# HID2AMI_Deluxe_Rev1_1_0_redist.net
KiCad netlist of a schematic drawn in EAGLE
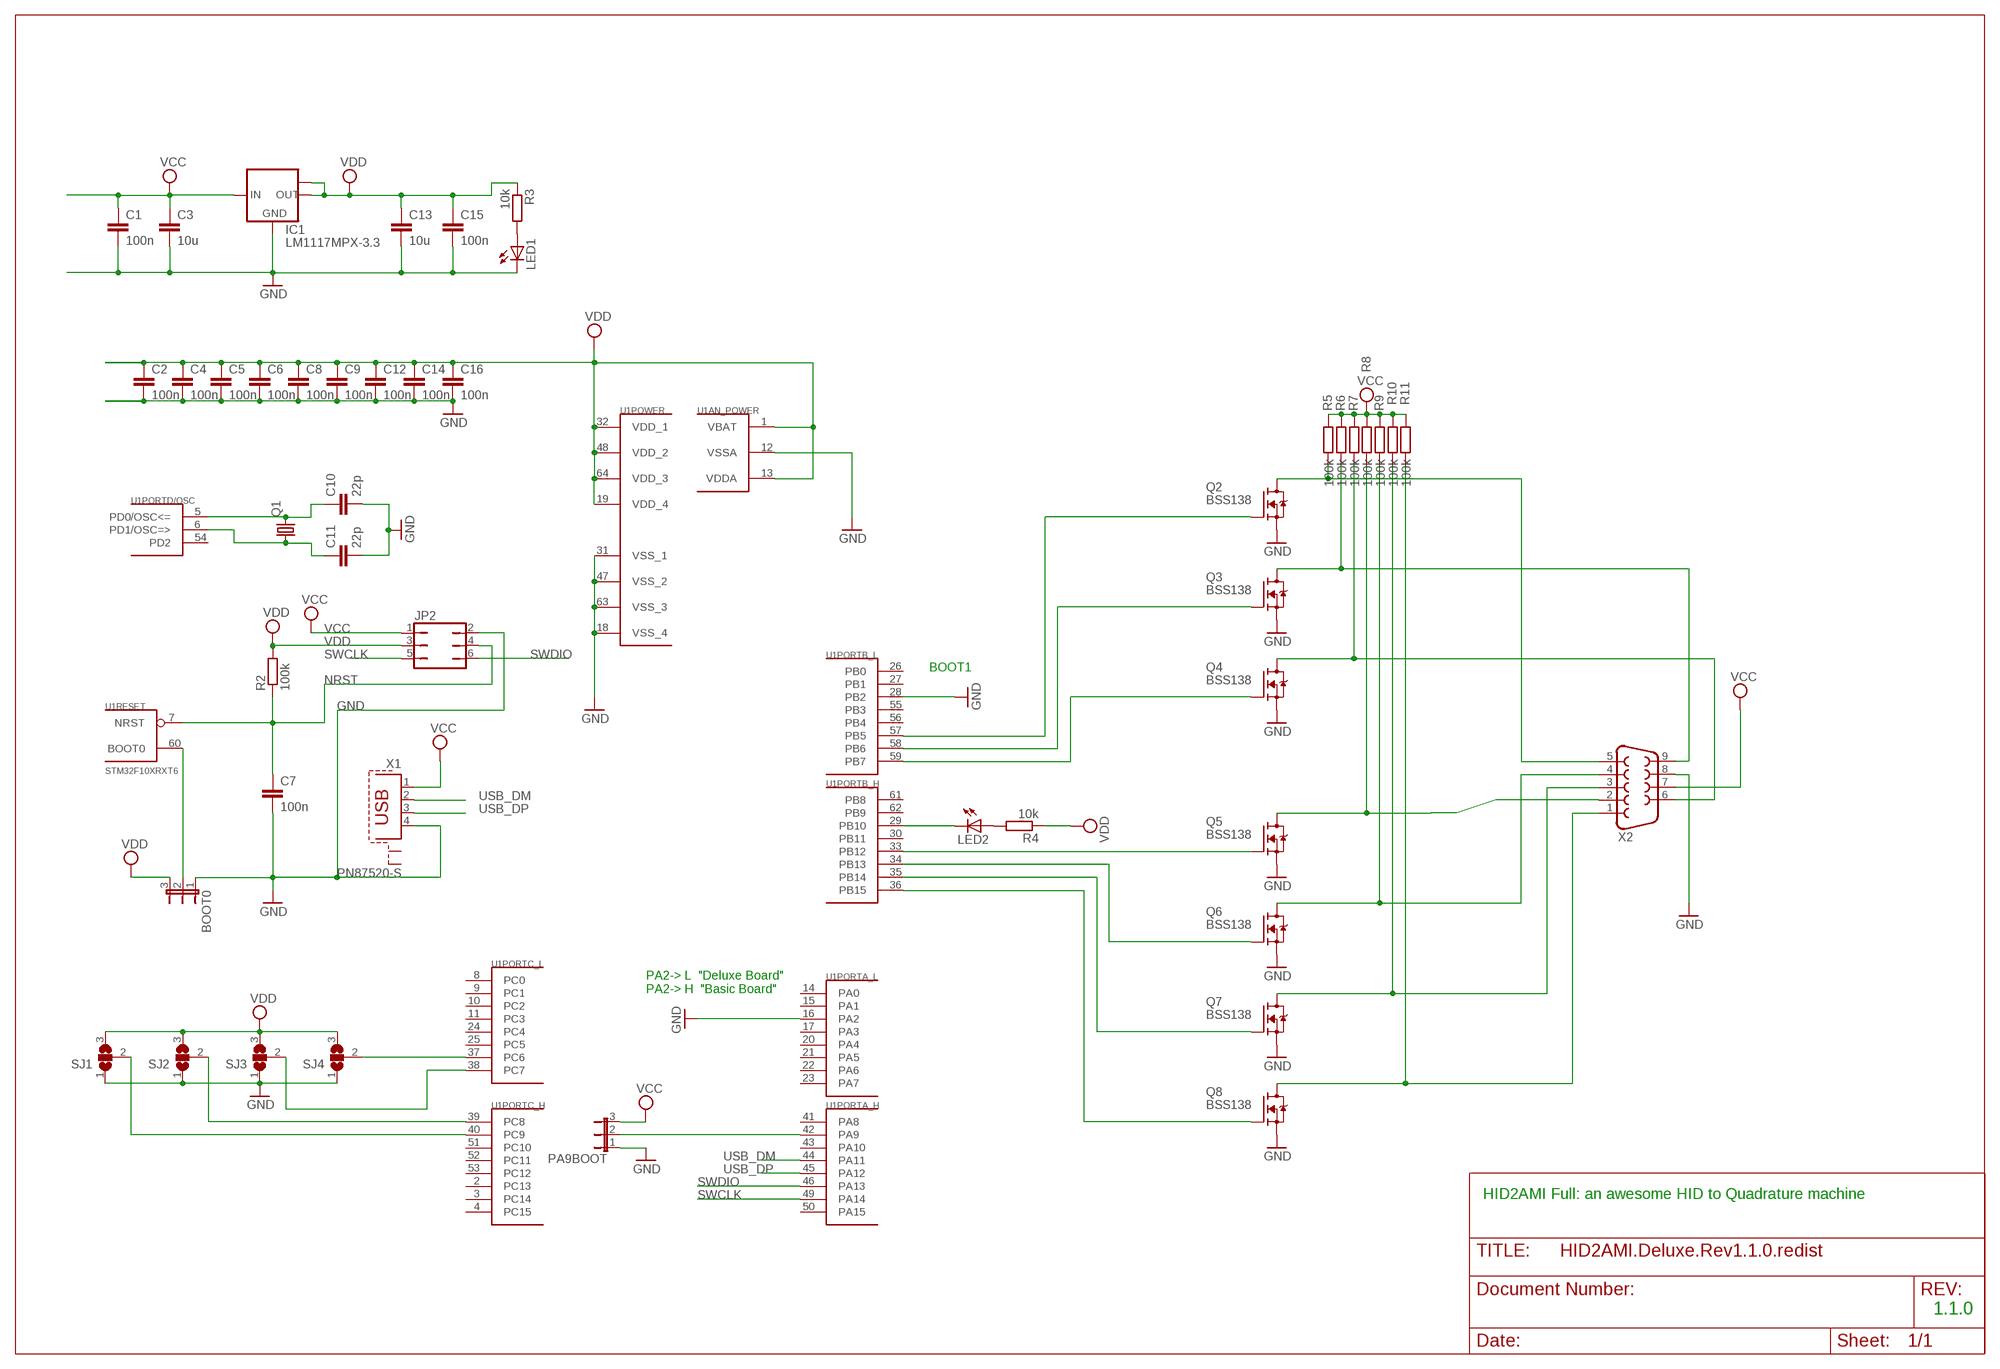
[diagram p0: schematic, sheet 1]

(export (version "E")
  (design (tool "Eeschema 10.0.6"))
  (components
    (comp (ref "BOOT0")
      (value "JP2E")
      (footprint "eagle-import:JP2")
      (libsource (lib "eagle-import") (part "JP2E"))
    )
    (comp (ref "C1")
      (value "100n")
      (footprint "eagle-import:C0805")
      (libsource (lib "eagle-import") (part "C-EUC0805"))
    )
    (comp (ref "C2")
      (value "100n")
      (footprint "eagle-import:C0805")
      (libsource (lib "eagle-import") (part "C-EUC0805"))
    )
    (comp (ref "C3")
      (value "10u")
      (footprint "eagle-import:C1206")
      (libsource (lib "eagle-import") (part "C-EUC1206"))
    )
    (comp (ref "C4")
      (value "100n")
      (footprint "eagle-import:C0805")
      (libsource (lib "eagle-import") (part "C-EUC0805"))
    )
    (comp (ref "C5")
      (value "100n")
      (footprint "eagle-import:C0805")
      (libsource (lib "eagle-import") (part "C-EUC0805"))
    )
    (comp (ref "C6")
      (value "100n")
      (footprint "eagle-import:C0805")
      (libsource (lib "eagle-import") (part "C-EUC0805"))
    )
    (comp (ref "C7")
      (value "100n")
      (footprint "eagle-import:C0805")
      (libsource (lib "eagle-import") (part "C-EUC0805"))
    )
    (comp (ref "C8")
      (value "100n")
      (footprint "eagle-import:C0805")
      (libsource (lib "eagle-import") (part "C-EUC0805"))
    )
    (comp (ref "C9")
      (value "100n")
      (footprint "eagle-import:C0805")
      (libsource (lib "eagle-import") (part "C-EUC0805"))
    )
    (comp (ref "C10")
      (value "22p")
      (footprint "eagle-import:C0805")
      (libsource (lib "eagle-import") (part "C-EUC0805"))
    )
    (comp (ref "C11")
      (value "22p")
      (footprint "eagle-import:C0805")
      (libsource (lib "eagle-import") (part "C-EUC0805"))
    )
    (comp (ref "C12")
      (value "100n")
      (footprint "eagle-import:C0805")
      (libsource (lib "eagle-import") (part "C-EUC0805"))
    )
    (comp (ref "C13")
      (value "10u")
      (footprint "eagle-import:C0805")
      (libsource (lib "eagle-import") (part "C-EUC0805"))
    )
    (comp (ref "C14")
      (value "100n")
      (footprint "eagle-import:C0805")
      (libsource (lib "eagle-import") (part "C-EUC0805"))
    )
    (comp (ref "C15")
      (value "100n")
      (footprint "eagle-import:C0805")
      (libsource (lib "eagle-import") (part "C-EUC0805"))
    )
    (comp (ref "C16")
      (value "100n")
      (footprint "eagle-import:C0805")
      (libsource (lib "eagle-import") (part "C-EUC0805"))
    )
    (comp (ref "IC1")
      (value "LM1117MPX-3.3")
      (footprint "eagle-import:SOT223")
      (libsource (lib "eagle-import") (part "LM1117MPX-3.3"))
    )
    (comp (ref "JP2")
      (value "JP3Q")
      (footprint "eagle-import:JP3Q")
      (libsource (lib "eagle-import") (part "JP3Q"))
    )
    (comp (ref "LED1")
      (value "LEDSML0805")
      (footprint "eagle-import:SML0805")
      (libsource (lib "eagle-import") (part "LEDSML0805"))
    )
    (comp (ref "LED2")
      (value "LEDSML0805")
      (footprint "eagle-import:SML0805")
      (libsource (lib "eagle-import") (part "LEDSML0805"))
    )
    (comp (ref "PA9BOOT")
      (value "JP2E")
      (footprint "eagle-import:JP2")
      (libsource (lib "eagle-import") (part "JP2E"))
    )
    (comp (ref "Q1")
      (value "CRYSTALHC49S")
      (footprint "eagle-import:HC49_S")
      (libsource (lib "eagle-import") (part "CRYSTALHC49S"))
    )
    (comp (ref "Q2")
      (value "BSS138")
      (footprint "eagle-import:SOT23")
      (fields (field (name "MF") "Fairchild"))
      (libsource (lib "eagle-import") (part "BSS138"))
    )
    (comp (ref "Q3")
      (value "BSS138")
      (footprint "eagle-import:SOT23")
      (fields (field (name "MF") "Fairchild"))
      (libsource (lib "eagle-import") (part "BSS138"))
    )
    (comp (ref "Q4")
      (value "BSS138")
      (footprint "eagle-import:SOT23")
      (fields (field (name "MF") "Fairchild"))
      (libsource (lib "eagle-import") (part "BSS138"))
    )
    (comp (ref "Q5")
      (value "BSS138")
      (footprint "eagle-import:SOT23")
      (fields (field (name "MF") "Fairchild"))
      (libsource (lib "eagle-import") (part "BSS138"))
    )
    (comp (ref "Q6")
      (value "BSS138")
      (footprint "eagle-import:SOT23")
      (fields (field (name "MF") "Fairchild"))
      (libsource (lib "eagle-import") (part "BSS138"))
    )
    (comp (ref "Q7")
      (value "BSS138")
      (footprint "eagle-import:SOT23")
      (fields (field (name "MF") "Fairchild"))
      (libsource (lib "eagle-import") (part "BSS138"))
    )
    (comp (ref "Q8")
      (value "BSS138")
      (footprint "eagle-import:SOT23")
      (fields (field (name "MF") "Fairchild"))
      (libsource (lib "eagle-import") (part "BSS138"))
    )
    (comp (ref "R2")
      (value "100k")
      (footprint "eagle-import:M0805")
      (libsource (lib "eagle-import") (part "R-EU_M0805"))
    )
    (comp (ref "R3")
      (value "10k")
      (footprint "eagle-import:M0805")
      (libsource (lib "eagle-import") (part "R-EU_M0805"))
    )
    (comp (ref "R4")
      (value "10k")
      (footprint "eagle-import:M0805")
      (libsource (lib "eagle-import") (part "R-EU_M0805"))
    )
    (comp (ref "R5")
      (value "100k")
      (footprint "eagle-import:M0805")
      (libsource (lib "eagle-import") (part "R-EU_M0805"))
    )
    (comp (ref "R6")
      (value "100k")
      (footprint "eagle-import:M0805")
      (libsource (lib "eagle-import") (part "R-EU_M0805"))
    )
    (comp (ref "R7")
      (value "100k")
      (footprint "eagle-import:M0805")
      (libsource (lib "eagle-import") (part "R-EU_M0805"))
    )
    (comp (ref "R8")
      (value "100k")
      (footprint "eagle-import:M0805")
      (libsource (lib "eagle-import") (part "R-EU_M0805"))
    )
    (comp (ref "R9")
      (value "100k")
      (footprint "eagle-import:M0805")
      (libsource (lib "eagle-import") (part "R-EU_M0805"))
    )
    (comp (ref "R10")
      (value "100k")
      (footprint "eagle-import:M0805")
      (libsource (lib "eagle-import") (part "R-EU_M0805"))
    )
    (comp (ref "R11")
      (value "100k")
      (footprint "eagle-import:M0805")
      (libsource (lib "eagle-import") (part "R-EU_M0805"))
    )
    (comp (ref "SJ1")
      (value "SJ2W")
      (footprint "eagle-import:SJ_2")
      (libsource (lib "eagle-import") (part "SJ2W"))
    )
    (comp (ref "SJ2")
      (value "SJ2W")
      (footprint "eagle-import:SJ_2")
      (libsource (lib "eagle-import") (part "SJ2W"))
    )
    (comp (ref "SJ3")
      (value "SJ2W")
      (footprint "eagle-import:SJ_2")
      (libsource (lib "eagle-import") (part "SJ2W"))
    )
    (comp (ref "SJ4")
      (value "SJ2W")
      (footprint "eagle-import:SJ_2")
      (libsource (lib "eagle-import") (part "SJ2W"))
    )
    (comp (ref "U1")
      (value "STM32F10XRXT6")
      (footprint "eagle-import:TQFP64")
      (libsource (lib "eagle-import") (part "STM32F10XRXT6"))
    )
    (comp (ref "X1")
      (value "PN87520-S")
      (footprint "eagle-import:PN87520-S")
      (libsource (lib "eagle-import") (part "PN87520-S"))
    )
    (comp (ref "X2")
      (value "F09HP")
      (footprint "eagle-import:F09HP")
      (libsource (lib "eagle-import") (part "F09HP"))
    )
  )
  (nets
    (net (code "1") (name "/NRST") (class "Default")
      (node (ref "C7") (pin "1") (pinfunction "1_1") (pintype "passive"))
      (node (ref "JP2") (pin "4") (pinfunction "4_4") (pintype "passive"))
      (node (ref "R2") (pin "1") (pinfunction "1_1") (pintype "passive"))
      (node (ref "U1") (pin "7") (pinfunction "NRST_7") (pintype "input"))
    )
    (net (code "2") (name "/SWCLK") (class "Default")
      (node (ref "JP2") (pin "5") (pinfunction "5_5") (pintype "passive"))
      (node (ref "U1") (pin "49") (pinfunction "PA14_49") (pintype "bidirectional"))
    )
    (net (code "3") (name "/SWDIO") (class "Default")
      (node (ref "JP2") (pin "6") (pinfunction "6_6") (pintype "passive"))
      (node (ref "U1") (pin "46") (pinfunction "PA13_46") (pintype "bidirectional"))
    )
    (net (code "4") (name "/USB_DM") (class "Default")
      (node (ref "U1") (pin "44") (pinfunction "PA11_44") (pintype "bidirectional"))
      (node (ref "X1") (pin "2") (pinfunction "2_2") (pintype "passive"))
    )
    (net (code "5") (name "/USB_DP") (class "Default")
      (node (ref "U1") (pin "45") (pinfunction "PA12_45") (pintype "bidirectional"))
      (node (ref "X1") (pin "3") (pinfunction "3_3") (pintype "passive"))
    )
    (net (code "6") (name "GND") (class "Default")
      (node (ref "BOOT0") (pin "1") (pinfunction "1_1") (pintype "passive"))
      (node (ref "C1") (pin "2") (pinfunction "2_2") (pintype "passive"))
      (node (ref "C10") (pin "2") (pinfunction "2_2") (pintype "passive"))
      (node (ref "C11") (pin "2") (pinfunction "2_2") (pintype "passive"))
      (node (ref "C12") (pin "2") (pinfunction "2_2") (pintype "passive"))
      (node (ref "C13") (pin "2") (pinfunction "2_2") (pintype "passive"))
      (node (ref "C14") (pin "2") (pinfunction "2_2") (pintype "passive"))
      (node (ref "C15") (pin "2") (pinfunction "2_2") (pintype "passive"))
      (node (ref "C16") (pin "2") (pinfunction "2_2") (pintype "passive"))
      (node (ref "C2") (pin "2") (pinfunction "2_2") (pintype "passive"))
      (node (ref "C3") (pin "2") (pinfunction "2_2") (pintype "passive"))
      (node (ref "C4") (pin "2") (pinfunction "2_2") (pintype "passive"))
      (node (ref "C5") (pin "2") (pinfunction "2_2") (pintype "passive"))
      (node (ref "C6") (pin "2") (pinfunction "2_2") (pintype "passive"))
      (node (ref "C7") (pin "2") (pinfunction "2_2") (pintype "passive"))
      (node (ref "C8") (pin "2") (pinfunction "2_2") (pintype "passive"))
      (node (ref "C9") (pin "2") (pinfunction "2_2") (pintype "passive"))
      (node (ref "IC1") (pin "1") (pinfunction "GND_1") (pintype "input"))
      (node (ref "JP2") (pin "2") (pinfunction "2_2") (pintype "passive"))
      (node (ref "LED1") (pin "C") (pinfunction "C_C") (pintype "passive"))
      (node (ref "PA9BOOT") (pin "1") (pinfunction "1_1") (pintype "passive"))
      (node (ref "Q2") (pin "2") (pinfunction "S_2") (pintype "passive"))
      (node (ref "Q3") (pin "2") (pinfunction "S_2") (pintype "passive"))
      (node (ref "Q4") (pin "2") (pinfunction "S_2") (pintype "passive"))
      (node (ref "Q5") (pin "2") (pinfunction "S_2") (pintype "passive"))
      (node (ref "Q6") (pin "2") (pinfunction "S_2") (pintype "passive"))
      (node (ref "Q7") (pin "2") (pinfunction "S_2") (pintype "passive"))
      (node (ref "Q8") (pin "2") (pinfunction "S_2") (pintype "passive"))
      (node (ref "SJ1") (pin "1") (pinfunction "1_1") (pintype "passive"))
      (node (ref "SJ2") (pin "1") (pinfunction "1_1") (pintype "passive"))
      (node (ref "SJ3") (pin "1") (pinfunction "1_1") (pintype "passive"))
      (node (ref "SJ4") (pin "1") (pinfunction "1_1") (pintype "passive"))
      (node (ref "U1") (pin "12") (pinfunction "VSSA_12") (pintype "power_in"))
      (node (ref "U1") (pin "16") (pinfunction "PA2_16") (pintype "bidirectional"))
      (node (ref "U1") (pin "18") (pinfunction "VSS_4_18") (pintype "power_in"))
      (node (ref "U1") (pin "28") (pinfunction "PB2_28") (pintype "bidirectional"))
      (node (ref "U1") (pin "31") (pinfunction "VSS_1_31") (pintype "power_in"))
      (node (ref "U1") (pin "47") (pinfunction "VSS_2_47") (pintype "power_in"))
      (node (ref "U1") (pin "63") (pinfunction "VSS_3_63") (pintype "power_in"))
      (node (ref "X1") (pin "4") (pinfunction "4_4") (pintype "passive"))
      (node (ref "X2") (pin "8") (pinfunction "8_8") (pintype "passive"))
    )
    (net (code "7") (name "Net-(LED1-PadA)") (class "Default")
      (node (ref "LED1") (pin "A") (pinfunction "A_A") (pintype "passive"))
      (node (ref "R3") (pin "2") (pinfunction "2_2") (pintype "passive"))
    )
    (net (code "8") (name "Net-(LED2-PadA)") (class "Default")
      (node (ref "LED2") (pin "A") (pinfunction "A_A") (pintype "passive"))
      (node (ref "R4") (pin "2") (pinfunction "2_2") (pintype "passive"))
    )
    (net (code "9") (name "Net-(Q2-D)") (class "Default")
      (node (ref "Q2") (pin "3") (pinfunction "D_3") (pintype "passive"))
      (node (ref "R5") (pin "2") (pinfunction "2_2") (pintype "passive"))
      (node (ref "X2") (pin "5") (pinfunction "5_5") (pintype "passive"))
    )
    (net (code "10") (name "Net-(Q2-G)") (class "Default")
      (node (ref "Q2") (pin "1") (pinfunction "G_1") (pintype "passive"))
      (node (ref "U1") (pin "57") (pinfunction "PB5_57") (pintype "bidirectional"))
    )
    (net (code "11") (name "Net-(Q3-D)") (class "Default")
      (node (ref "Q3") (pin "3") (pinfunction "D_3") (pintype "passive"))
      (node (ref "R6") (pin "2") (pinfunction "2_2") (pintype "passive"))
      (node (ref "X2") (pin "9") (pinfunction "9_9") (pintype "passive"))
    )
    (net (code "12") (name "Net-(Q3-G)") (class "Default")
      (node (ref "Q3") (pin "1") (pinfunction "G_1") (pintype "passive"))
      (node (ref "U1") (pin "58") (pinfunction "PB6_58") (pintype "bidirectional"))
    )
    (net (code "13") (name "Net-(Q4-D)") (class "Default")
      (node (ref "Q4") (pin "3") (pinfunction "D_3") (pintype "passive"))
      (node (ref "R7") (pin "2") (pinfunction "2_2") (pintype "passive"))
      (node (ref "X2") (pin "6") (pinfunction "6_6") (pintype "passive"))
    )
    (net (code "14") (name "Net-(Q4-G)") (class "Default")
      (node (ref "Q4") (pin "1") (pinfunction "G_1") (pintype "passive"))
      (node (ref "U1") (pin "59") (pinfunction "PB7_59") (pintype "bidirectional"))
    )
    (net (code "15") (name "Net-(Q5-D)") (class "Default")
      (node (ref "Q5") (pin "3") (pinfunction "D_3") (pintype "passive"))
      (node (ref "R8") (pin "2") (pinfunction "2_2") (pintype "passive"))
      (node (ref "X2") (pin "2") (pinfunction "2_2") (pintype "passive"))
    )
    (net (code "16") (name "Net-(Q5-G)") (class "Default")
      (node (ref "Q5") (pin "1") (pinfunction "G_1") (pintype "passive"))
      (node (ref "U1") (pin "33") (pinfunction "PB12_33") (pintype "bidirectional"))
    )
    (net (code "17") (name "Net-(Q6-D)") (class "Default")
      (node (ref "Q6") (pin "3") (pinfunction "D_3") (pintype "passive"))
      (node (ref "R9") (pin "2") (pinfunction "2_2") (pintype "passive"))
      (node (ref "X2") (pin "4") (pinfunction "4_4") (pintype "passive"))
    )
    (net (code "18") (name "Net-(Q6-G)") (class "Default")
      (node (ref "Q6") (pin "1") (pinfunction "G_1") (pintype "passive"))
      (node (ref "U1") (pin "34") (pinfunction "PB13_34") (pintype "bidirectional"))
    )
    (net (code "19") (name "Net-(Q7-D)") (class "Default")
      (node (ref "Q7") (pin "3") (pinfunction "D_3") (pintype "passive"))
      (node (ref "R10") (pin "2") (pinfunction "2_2") (pintype "passive"))
      (node (ref "X2") (pin "3") (pinfunction "3_3") (pintype "passive"))
    )
    (net (code "20") (name "Net-(Q7-G)") (class "Default")
      (node (ref "Q7") (pin "1") (pinfunction "G_1") (pintype "passive"))
      (node (ref "U1") (pin "35") (pinfunction "PB14_35") (pintype "bidirectional"))
    )
    (net (code "21") (name "Net-(Q8-D)") (class "Default")
      (node (ref "Q8") (pin "3") (pinfunction "D_3") (pintype "passive"))
      (node (ref "R11") (pin "2") (pinfunction "2_2") (pintype "passive"))
      (node (ref "X2") (pin "1") (pinfunction "1_1") (pintype "passive"))
    )
    (net (code "22") (name "Net-(Q8-G)") (class "Default")
      (node (ref "Q8") (pin "1") (pinfunction "G_1") (pintype "passive"))
      (node (ref "U1") (pin "36") (pinfunction "PB15_36") (pintype "bidirectional"))
    )
    (net (code "23") (name "Net-(U1B-PA9)") (class "Default")
      (node (ref "PA9BOOT") (pin "2") (pinfunction "2_2") (pintype "passive"))
      (node (ref "U1") (pin "42") (pinfunction "PA9_42") (pintype "bidirectional"))
    )
    (net (code "24") (name "Net-(U1D-PB10)") (class "Default")
      (node (ref "LED2") (pin "C") (pinfunction "C_C") (pintype "passive"))
      (node (ref "U1") (pin "29") (pinfunction "PB10_29") (pintype "bidirectional"))
    )
    (net (code "25") (name "Net-(U1F-PC8)") (class "Default")
      (node (ref "SJ2") (pin "2") (pinfunction "2_2") (pintype "passive"))
      (node (ref "U1") (pin "39") (pinfunction "PC8_39") (pintype "bidirectional"))
    )
    (net (code "26") (name "Net-(U1F-PC9)") (class "Default")
      (node (ref "SJ1") (pin "2") (pinfunction "2_2") (pintype "passive"))
      (node (ref "U1") (pin "40") (pinfunction "PC9_40") (pintype "bidirectional"))
    )
    (net (code "27") (name "Net-(U1G-PC6)") (class "Default")
      (node (ref "SJ4") (pin "2") (pinfunction "2_2") (pintype "passive"))
      (node (ref "U1") (pin "37") (pinfunction "PC6_37") (pintype "bidirectional"))
    )
    (net (code "28") (name "Net-(U1G-PC7)") (class "Default")
      (node (ref "SJ3") (pin "2") (pinfunction "2_2") (pintype "passive"))
      (node (ref "U1") (pin "38") (pinfunction "PC7_38") (pintype "bidirectional"))
    )
    (net (code "29") (name "Net-(U1H-PD0{slash}OSC<=)") (class "Default")
      (node (ref "C10") (pin "1") (pinfunction "1_1") (pintype "passive"))
      (node (ref "Q1") (pin "2") (pinfunction "2_2") (pintype "passive"))
      (node (ref "U1") (pin "5") (pinfunction "PD0/OSC<=_5") (pintype "bidirectional"))
    )
    (net (code "30") (name "Net-(U1H-PD1{slash}OSC=>)") (class "Default")
      (node (ref "C11") (pin "1") (pinfunction "1_1") (pintype "passive"))
      (node (ref "Q1") (pin "1") (pinfunction "1_1") (pintype "passive"))
      (node (ref "U1") (pin "6") (pinfunction "PD1/OSC=>_6") (pintype "bidirectional"))
    )
    (net (code "31") (name "Net-(U1J-BOOT0)") (class "Default")
      (node (ref "BOOT0") (pin "2") (pinfunction "2_2") (pintype "passive"))
      (node (ref "U1") (pin "60") (pinfunction "BOOT0_60") (pintype "input"))
    )
    (net (code "32") (name "VCC") (class "Default")
      (node (ref "C1") (pin "1") (pinfunction "1_1") (pintype "passive"))
      (node (ref "C3") (pin "1") (pinfunction "1_1") (pintype "passive"))
      (node (ref "IC1") (pin "3") (pinfunction "IN_3") (pintype "input"))
      (node (ref "JP2") (pin "1") (pinfunction "1_1") (pintype "passive"))
      (node (ref "PA9BOOT") (pin "3") (pinfunction "3_3") (pintype "passive"))
      (node (ref "R10") (pin "1") (pinfunction "1_1") (pintype "passive"))
      (node (ref "R11") (pin "1") (pinfunction "1_1") (pintype "passive"))
      (node (ref "R5") (pin "1") (pinfunction "1_1") (pintype "passive"))
      (node (ref "R6") (pin "1") (pinfunction "1_1") (pintype "passive"))
      (node (ref "R7") (pin "1") (pinfunction "1_1") (pintype "passive"))
      (node (ref "R8") (pin "1") (pinfunction "1_1") (pintype "passive"))
      (node (ref "R9") (pin "1") (pinfunction "1_1") (pintype "passive"))
      (node (ref "X1") (pin "1") (pinfunction "1_1") (pintype "passive"))
      (node (ref "X2") (pin "7") (pinfunction "7_7") (pintype "passive"))
    )
    (net (code "33") (name "VDD") (class "Default")
      (node (ref "BOOT0") (pin "3") (pinfunction "3_3") (pintype "passive"))
      (node (ref "C12") (pin "1") (pinfunction "1_1") (pintype "passive"))
      (node (ref "C13") (pin "1") (pinfunction "1_1") (pintype "passive"))
      (node (ref "C14") (pin "1") (pinfunction "1_1") (pintype "passive"))
      (node (ref "C15") (pin "1") (pinfunction "1_1") (pintype "passive"))
      (node (ref "C16") (pin "1") (pinfunction "1_1") (pintype "passive"))
      (node (ref "C2") (pin "1") (pinfunction "1_1") (pintype "passive"))
      (node (ref "C4") (pin "1") (pinfunction "1_1") (pintype "passive"))
      (node (ref "C5") (pin "1") (pinfunction "1_1") (pintype "passive"))
      (node (ref "C6") (pin "1") (pinfunction "1_1") (pintype "passive"))
      (node (ref "C8") (pin "1") (pinfunction "1_1") (pintype "passive"))
      (node (ref "C9") (pin "1") (pinfunction "1_1") (pintype "passive"))
      (node (ref "IC1") (pin "2") (pinfunction "OUT_2") (pintype "passive"))
      (node (ref "IC1") (pin "TAB") (pinfunction "OUT1_TAB") (pintype "passive"))
      (node (ref "JP2") (pin "3") (pinfunction "3_3") (pintype "passive"))
      (node (ref "R2") (pin "2") (pinfunction "2_2") (pintype "passive"))
      (node (ref "R3") (pin "1") (pinfunction "1_1") (pintype "passive"))
      (node (ref "R4") (pin "1") (pinfunction "1_1") (pintype "passive"))
      (node (ref "SJ1") (pin "3") (pinfunction "3_3") (pintype "passive"))
      (node (ref "SJ2") (pin "3") (pinfunction "3_3") (pintype "passive"))
      (node (ref "SJ3") (pin "3") (pinfunction "3_3") (pintype "passive"))
      (node (ref "SJ4") (pin "3") (pinfunction "3_3") (pintype "passive"))
      (node (ref "U1") (pin "1") (pinfunction "VBAT_1") (pintype "power_in"))
      (node (ref "U1") (pin "13") (pinfunction "VDDA_13") (pintype "power_in"))
      (node (ref "U1") (pin "19") (pinfunction "VDD_4_19") (pintype "power_in"))
      (node (ref "U1") (pin "32") (pinfunction "VDD_1_32") (pintype "power_in"))
      (node (ref "U1") (pin "48") (pinfunction "VDD_2_48") (pintype "power_in"))
      (node (ref "U1") (pin "64") (pinfunction "VDD_3_64") (pintype "power_in"))
    )
    (net (code "34") (name "unconnected-(U1B-PA8-Pad41)") (class "Default")
      (node (ref "U1") (pin "41") (pinfunction "PA8_41") (pintype "bidirectional"))
    )
    (net (code "35") (name "unconnected-(U1B-PA10-Pad43)") (class "Default")
      (node (ref "U1") (pin "43") (pinfunction "PA10_43") (pintype "bidirectional"))
    )
    (net (code "36") (name "unconnected-(U1B-PA15-Pad50)") (class "Default")
      (node (ref "U1") (pin "50") (pinfunction "PA15_50") (pintype "bidirectional"))
    )
    (net (code "37") (name "unconnected-(U1C-PA0-Pad14)") (class "Default")
      (node (ref "U1") (pin "14") (pinfunction "PA0_14") (pintype "bidirectional"))
    )
    (net (code "38") (name "unconnected-(U1C-PA1-Pad15)") (class "Default")
      (node (ref "U1") (pin "15") (pinfunction "PA1_15") (pintype "bidirectional"))
    )
    (net (code "39") (name "unconnected-(U1C-PA3-Pad17)") (class "Default")
      (node (ref "U1") (pin "17") (pinfunction "PA3_17") (pintype "bidirectional"))
    )
    (net (code "40") (name "unconnected-(U1C-PA4-Pad20)") (class "Default")
      (node (ref "U1") (pin "20") (pinfunction "PA4_20") (pintype "bidirectional"))
    )
    (net (code "41") (name "unconnected-(U1C-PA5-Pad21)") (class "Default")
      (node (ref "U1") (pin "21") (pinfunction "PA5_21") (pintype "bidirectional"))
    )
    (net (code "42") (name "unconnected-(U1C-PA6-Pad22)") (class "Default")
      (node (ref "U1") (pin "22") (pinfunction "PA6_22") (pintype "bidirectional"))
    )
    (net (code "43") (name "unconnected-(U1C-PA7-Pad23)") (class "Default")
      (node (ref "U1") (pin "23") (pinfunction "PA7_23") (pintype "bidirectional"))
    )
    (net (code "44") (name "unconnected-(U1D-PB8-Pad61)") (class "Default")
      (node (ref "U1") (pin "61") (pinfunction "PB8_61") (pintype "bidirectional"))
    )
    (net (code "45") (name "unconnected-(U1D-PB9-Pad62)") (class "Default")
      (node (ref "U1") (pin "62") (pinfunction "PB9_62") (pintype "bidirectional"))
    )
    (net (code "46") (name "unconnected-(U1D-PB11-Pad30)") (class "Default")
      (node (ref "U1") (pin "30") (pinfunction "PB11_30") (pintype "bidirectional"))
    )
    (net (code "47") (name "unconnected-(U1E-PB0-Pad26)") (class "Default")
      (node (ref "U1") (pin "26") (pinfunction "PB0_26") (pintype "bidirectional"))
    )
    (net (code "48") (name "unconnected-(U1E-PB1-Pad27)") (class "Default")
      (node (ref "U1") (pin "27") (pinfunction "PB1_27") (pintype "bidirectional"))
    )
    (net (code "49") (name "unconnected-(U1E-PB3-Pad55)") (class "Default")
      (node (ref "U1") (pin "55") (pinfunction "PB3_55") (pintype "bidirectional"))
    )
    (net (code "50") (name "unconnected-(U1E-PB4-Pad56)") (class "Default")
      (node (ref "U1") (pin "56") (pinfunction "PB4_56") (pintype "bidirectional"))
    )
    (net (code "51") (name "unconnected-(U1F-PC10-Pad51)") (class "Default")
      (node (ref "U1") (pin "51") (pinfunction "PC10_51") (pintype "bidirectional"))
    )
    (net (code "52") (name "unconnected-(U1F-PC11-Pad52)") (class "Default")
      (node (ref "U1") (pin "52") (pinfunction "PC11_52") (pintype "bidirectional"))
    )
    (net (code "53") (name "unconnected-(U1F-PC12-Pad53)") (class "Default")
      (node (ref "U1") (pin "53") (pinfunction "PC12_53") (pintype "bidirectional"))
    )
    (net (code "54") (name "unconnected-(U1F-PC13-Pad2)") (class "Default")
      (node (ref "U1") (pin "2") (pinfunction "PC13_2") (pintype "bidirectional"))
    )
    (net (code "55") (name "unconnected-(U1F-PC14-Pad3)") (class "Default")
      (node (ref "U1") (pin "3") (pinfunction "PC14_3") (pintype "bidirectional"))
    )
    (net (code "56") (name "unconnected-(U1F-PC15-Pad4)") (class "Default")
      (node (ref "U1") (pin "4") (pinfunction "PC15_4") (pintype "bidirectional"))
    )
    (net (code "57") (name "unconnected-(U1G-PC0-Pad8)") (class "Default")
      (node (ref "U1") (pin "8") (pinfunction "PC0_8") (pintype "bidirectional"))
    )
    (net (code "58") (name "unconnected-(U1G-PC1-Pad9)") (class "Default")
      (node (ref "U1") (pin "9") (pinfunction "PC1_9") (pintype "bidirectional"))
    )
    (net (code "59") (name "unconnected-(U1G-PC2-Pad10)") (class "Default")
      (node (ref "U1") (pin "10") (pinfunction "PC2_10") (pintype "bidirectional"))
    )
    (net (code "60") (name "unconnected-(U1G-PC3-Pad11)") (class "Default")
      (node (ref "U1") (pin "11") (pinfunction "PC3_11") (pintype "bidirectional"))
    )
    (net (code "61") (name "unconnected-(U1G-PC4-Pad24)") (class "Default")
      (node (ref "U1") (pin "24") (pinfunction "PC4_24") (pintype "bidirectional"))
    )
    (net (code "62") (name "unconnected-(U1G-PC5-Pad25)") (class "Default")
      (node (ref "U1") (pin "25") (pinfunction "PC5_25") (pintype "bidirectional"))
    )
    (net (code "63") (name "unconnected-(U1H-PD2-Pad54)") (class "Default")
      (node (ref "U1") (pin "54") (pinfunction "PD2_54") (pintype "bidirectional"))
    )
    (net (code "64") (name "unconnected-(X1-PadS1)") (class "Default")
      (node (ref "X1") (pin "S1") (pinfunction "S1_S1") (pintype "passive"))
    )
    (net (code "65") (name "unconnected-(X1-PadS2)") (class "Default")
      (node (ref "X1") (pin "S2") (pinfunction "S2_S2") (pintype "passive"))
    )
  )
)
